# SH2_-_MCU.net
KiCad netlist of a schematic drawn in Altium Designer
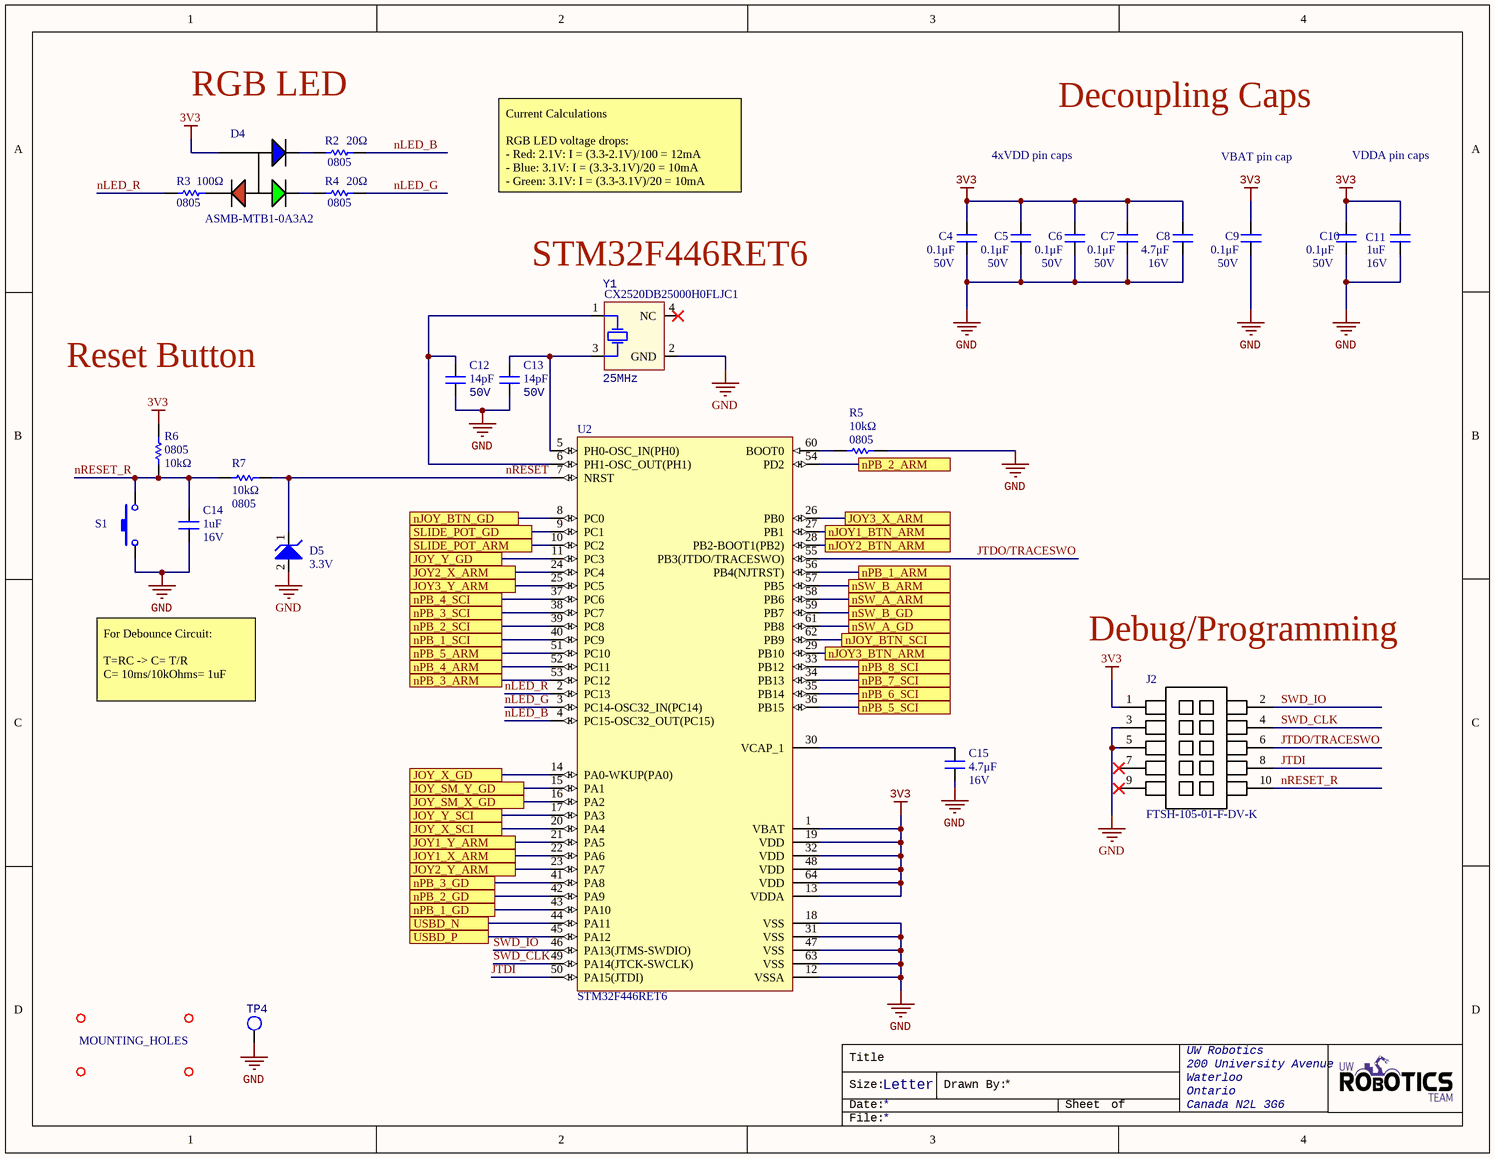
[diagram p0: SH2 - MCU.SchDoc]

(export (version "E")
  (design (tool "Eeschema 10.0.6"))
  (components
    (comp (ref "C4")
      (value "0.1μF")
      (footprint "CAPC2012X140N")
      (description "CAP CER 0.1UF 50V X7R 0805")
      (fields (field (name "TOLERANCE") "10%") (field (name "VOLTAGE RATING") "50V"))
      (libsource (lib "UWRT_Schematic_Library_2020") (part "CAP_0.1uF_50V_0805"))
    )
    (comp (ref "C5")
      (value "0.1μF")
      (footprint "CAPC2012X140N")
      (description "CAP CER 0.1UF 50V X7R 0805")
      (fields (field (name "TOLERANCE") "10%") (field (name "VOLTAGE RATING") "50V"))
      (libsource (lib "UWRT_Schematic_Library_2020") (part "CAP_0.1uF_50V_0805"))
    )
    (comp (ref "C6")
      (value "0.1μF")
      (footprint "CAPC2012X140N")
      (description "CAP CER 0.1UF 50V X7R 0805")
      (fields (field (name "TOLERANCE") "10%") (field (name "VOLTAGE RATING") "50V"))
      (libsource (lib "UWRT_Schematic_Library_2020") (part "CAP_0.1uF_50V_0805"))
    )
    (comp (ref "C7")
      (value "0.1μF")
      (footprint "CAPC2012X140N")
      (description "CAP CER 0.1UF 50V X7R 0805")
      (fields (field (name "TOLERANCE") "10%") (field (name "VOLTAGE RATING") "50V"))
      (libsource (lib "UWRT_Schematic_Library_2020") (part "CAP_0.1uF_50V_0805"))
    )
    (comp (ref "C8")
      (value "4.7μF")
      (footprint "CAPC2012X140N")
      (description "CAP CER 4.7UF 16V X5R 0805")
      (fields
        (field (name "TOLERANCE") "10%")
        (field (name "VOLTAGE RATING") "16V")
        (field (name "Comment") "CAP_4.7uF_16V_0805")
      )
      (libsource (lib "UWRT_Schematic_Library_2020") (part "CAP_4.7uF_16V_0805"))
    )
    (comp (ref "C9")
      (value "0.1μF")
      (footprint "CAPC2012X140N")
      (description "CAP CER 0.1UF 50V X7R 0805")
      (fields (field (name "TOLERANCE") "10%") (field (name "VOLTAGE RATING") "50V"))
      (libsource (lib "UWRT_Schematic_Library_2020") (part "CAP_0.1uF_50V_0805"))
    )
    (comp (ref "C10")
      (value "0.1μF")
      (footprint "CAPC2012X140N")
      (description "CAP CER 0.1UF 50V X7R 0805")
      (fields (field (name "TOLERANCE") "10%") (field (name "VOLTAGE RATING") "50V"))
      (libsource (lib "UWRT_Schematic_Library_2020") (part "CAP_0.1uF_50V_0805"))
    )
    (comp (ref "C11")
      (value "1uF")
      (footprint "CAPC2012X140N")
      (description "CAP CER 1UF 16V X7R 0805")
      (fields
        (field (name "TOLERANCE") "10%")
        (field (name "VOLTAGE RATING") "16V")
        (field (name "Comment") "CAP_1uF_16V_0805")
      )
      (libsource (lib "UWRT_Schematic_Library_2020") (part "CAP_1uF_16V_0805"))
    )
    (comp (ref "C12")
      (value "14pF")
      (footprint "CAPC0603(1608)55_N")
      (description "Cap Ceramic 14pF 50V C0G 5% SMD 0603 125C Cardboard T/R")
      (fields
        (field (name "TOLERANCE") "5%")
        (field (name "VOLTAGE RATING (DC)") "50V")
        (field (name "Comment") "CL10C140JB8NNNC")
      )
      (libsource (lib "UWRT_Schematic_Library_2020") (part "CL10C140JB8NNNC"))
    )
    (comp (ref "C13")
      (value "14pF")
      (footprint "CAPC0603(1608)55_N")
      (description "Cap Ceramic 14pF 50V C0G 5% SMD 0603 125C Cardboard T/R")
      (fields
        (field (name "TOLERANCE") "5%")
        (field (name "VOLTAGE RATING (DC)") "50V")
        (field (name "Comment") "CL10C140JB8NNNC")
      )
      (libsource (lib "UWRT_Schematic_Library_2020") (part "CL10C140JB8NNNC"))
    )
    (comp (ref "C14")
      (value "1uF")
      (footprint "CAPC2012X140N")
      (description "CAP CER 1UF 16V X7R 0805")
      (fields
        (field (name "TOLERANCE") "10%")
        (field (name "VOLTAGE RATING") "16V")
        (field (name "Comment") "CAP_1uF_16V_0805")
      )
      (libsource (lib "UWRT_Schematic_Library_2020") (part "CAP_1uF_16V_0805"))
    )
    (comp (ref "C15")
      (value "4.7μF")
      (footprint "CAPC2012X140N")
      (description "CAP CER 4.7UF 16V X5R 0805")
      (fields
        (field (name "TOLERANCE") "10%")
        (field (name "VOLTAGE RATING") "16V")
        (field (name "Comment") "CAP_4.7uF_16V_0805")
      )
      (libsource (lib "UWRT_Schematic_Library_2020") (part "CAP_4.7uF_16V_0805"))
    )
    (comp (ref "D4")
      (value "LED_RGB")
      (footprint "LED_RGB")
      (description "LED RGB DIFFUSED 4PLCC SMD")
      (fields (field (name "MANUFACTURER PART NUMBER 1") "ASMB-MTB1-0A3A2"))
      (libsource (lib "UWRT_Schematic_Library_2020") (part "LED_RGB"))
    )
    (comp (ref "D5")
      (value "TVS_DIODE_UNIDIR_3.3V")
      (footprint "SOD523")
      (description "TVS DIODE 3.3V 14.1V SOD523. Used to protect each connector input line going into the MCU.")
      (fields (field (name "REVERSE STANDOFF VOLTAGE") "3.3V"))
      (libsource (lib "UWRT_Schematic_Library_2020") (part "TVS_DIODE_UNIDIR_3.3V"))
    )
    (comp (ref "J2")
      (value "CON_PROGRAMMING")
      (footprint "FTSH-105-01-F-DV-K-P-TR")
      (fields (field (name "MANUFACTURER PART NUMBER 1") "FTSH-105-01-F-DV-K"))
      (libsource (lib "UWRT_Schematic_Library_2020") (part "CON_PROGRAMMING"))
    )
    (comp (ref "MH1")
      (value "MOUNTING_HOLES")
      (footprint "MOUNTING_HOLE")
      (description "6cm x 6cm")
      (libsource (lib "UWRT_Schematic_Library_2020") (part "MOUNTING_HOLES"))
    )
    (comp (ref "MH2")
      (value "MOUNTING_HOLES")
      (footprint "MOUNTING_HOLE")
      (description "6cm x 6cm")
      (libsource (lib "UWRT_Schematic_Library_2020") (part "MOUNTING_HOLES"))
    )
    (comp (ref "MH3")
      (value "MOUNTING_HOLES")
      (footprint "MOUNTING_HOLE")
      (description "6cm x 6cm")
      (libsource (lib "UWRT_Schematic_Library_2020") (part "MOUNTING_HOLES"))
    )
    (comp (ref "MH4")
      (value "MOUNTING_HOLES")
      (footprint "MOUNTING_HOLE")
      (description "6cm x 6cm")
      (libsource (lib "UWRT_Schematic_Library_2020") (part "MOUNTING_HOLES"))
    )
    (comp (ref "R2")
      (value "20Ω")
      (footprint "RESC2012X60N")
      (description "RES SMD 20 OHM 1% 1/8W 0805")
      (fields
        (field (name "CASE CODE (IMPERIAL)") "0805")
        (field (name "TOLERANCE") "1%")
        (field (name "Comment") "RES_20Ω_0805")
      )
      (libsource (lib "UWRT_Schematic_Library_2020") (part "RES_20Ω_0805"))
    )
    (comp (ref "R3")
      (value "100Ω")
      (footprint "RESC2012X60N")
      (description "RES SMD 100 OHM 1% 1/8W 0805")
      (fields (field (name "CASE CODE (IMPERIAL)") "0805") (field (name "Comment") "RES_100Ω_0805"))
      (libsource (lib "UWRT_Schematic_Library_2020") (part "RES_100Ω_0805"))
    )
    (comp (ref "R4")
      (value "20Ω")
      (footprint "RESC2012X60N")
      (description "RES SMD 20 OHM 1% 1/8W 0805")
      (fields
        (field (name "CASE CODE (IMPERIAL)") "0805")
        (field (name "TOLERANCE") "1%")
        (field (name "Comment") "RES_20Ω_0805")
      )
      (libsource (lib "UWRT_Schematic_Library_2020") (part "RES_20Ω_0805"))
    )
    (comp (ref "R5")
      (value "10kΩ")
      (footprint "RESC2012X60N")
      (description "RES SMD 10K OHM 1% 1/8W 0805")
      (fields
        (field (name "CASE CODE (IMPERIAL)") "0805")
        (field (name "TOLERANCE") "1%")
        (field (name "Comment") "RES_10kΩ_0805")
      )
      (libsource (lib "UWRT_Schematic_Library_2020") (part "RES_10kΩ_0805"))
    )
    (comp (ref "R6")
      (value "10kΩ")
      (footprint "RESC2012X60N")
      (description "RES SMD 10K OHM 1% 1/8W 0805")
      (fields
        (field (name "CASE CODE (IMPERIAL)") "0805")
        (field (name "TOLERANCE") "1%")
        (field (name "Comment") "RES_10kΩ_0805")
      )
      (libsource (lib "UWRT_Schematic_Library_2020") (part "RES_10kΩ_0805"))
    )
    (comp (ref "R7")
      (value "10kΩ")
      (footprint "RESC2012X60N")
      (description "RES SMD 10K OHM 1% 1/8W 0805")
      (fields
        (field (name "CASE CODE (IMPERIAL)") "0805")
        (field (name "TOLERANCE") "1%")
        (field (name "Comment") "RES_10kΩ_0805")
      )
      (libsource (lib "UWRT_Schematic_Library_2020") (part "RES_10kΩ_0805"))
    )
    (comp (ref "S1")
      (value "SW_TACTILE")
      (footprint "B3U-1000P")
      (description "Tactile Switch (Grey)")
      (libsource (lib "UWRT_Schematic_Library_2020") (part "SW_TACTILE"))
    )
    (comp (ref "TP4")
      (value "TESTPOINT_LOOP")
      (footprint "TESTPOINT_LOOP")
      (description "Loop testpoint through-hole pad")
      (libsource (lib "UWRT_Schematic_Library_2020") (part "TESTPOINT_LOOP"))
    )
    (comp (ref "U2")
      (value "STM32F446RET6")
      (footprint "STM-LQFP64_L")
      (libsource (lib "UWRT_Schematic_Library_2020") (part "MCU_STM32F446RET6"))
    )
    (comp (ref "Y1")
      (value "CRYSTAL_25MHZ")
      (footprint "SOIC254P1016X440-4N")
      (description "CRYSTAL 25.0000MHZ 12PF SMD")
      (fields
        (field (name "MANUFACTURER PART NUMBER 1") "CX2520DB25000H0FLJC1")
        (field (name "FREQUENCY") "25MHz")
      )
      (libsource (lib "UWRT_Schematic_Library_2020") (part "CRYSTAL_25MHZ"))
    )
  )
  (nets
    (net (code "1") (name "/JOY1_X_ARM") (class "Default")
      (node (ref "U2") (pin "22") (pinfunction "PA6_22") (pintype "bidirectional"))
    )
    (net (code "2") (name "/JOY1_Y_ARM") (class "Default")
      (node (ref "U2") (pin "21") (pinfunction "PA5_21") (pintype "bidirectional"))
    )
    (net (code "3") (name "/JOY2_X_ARM") (class "Default")
      (node (ref "U2") (pin "24") (pinfunction "PC4_24") (pintype "bidirectional"))
    )
    (net (code "4") (name "/JOY2_Y_ARM") (class "Default")
      (node (ref "U2") (pin "23") (pinfunction "PA7_23") (pintype "bidirectional"))
    )
    (net (code "5") (name "/JOY3_X_ARM") (class "Default")
      (node (ref "U2") (pin "26") (pinfunction "PB0_26") (pintype "bidirectional"))
    )
    (net (code "6") (name "/JOY3_Y_ARM") (class "Default")
      (node (ref "U2") (pin "25") (pinfunction "PC5_25") (pintype "bidirectional"))
    )
    (net (code "7") (name "/JOY_SM_X_GD") (class "Default")
      (node (ref "U2") (pin "16") (pinfunction "PA2_16") (pintype "bidirectional"))
    )
    (net (code "8") (name "/JOY_SM_Y_GD") (class "Default")
      (node (ref "U2") (pin "15") (pinfunction "PA1_15") (pintype "bidirectional"))
    )
    (net (code "9") (name "/JOY_X_GD") (class "Default")
      (node (ref "U2") (pin "14") (pinfunction "PA0-WKUP(PA0)_14") (pintype "bidirectional"))
    )
    (net (code "10") (name "/JOY_X_SCI") (class "Default")
      (node (ref "U2") (pin "20") (pinfunction "PA4_20") (pintype "bidirectional"))
    )
    (net (code "11") (name "/JOY_Y_GD") (class "Default")
      (node (ref "U2") (pin "11") (pinfunction "PC3_11") (pintype "bidirectional"))
    )
    (net (code "12") (name "/JOY_Y_SCI") (class "Default")
      (node (ref "U2") (pin "17") (pinfunction "PA3_17") (pintype "bidirectional"))
    )
    (net (code "13") (name "/JTDI") (class "Default")
      (node (ref "J2") (pin "8") (pinfunction "8_8") (pintype "passive"))
      (node (ref "U2") (pin "50") (pinfunction "PA15(JTDI)_50") (pintype "bidirectional"))
    )
    (net (code "14") (name "/JTDO{slash}TRACESWO") (class "Default")
      (node (ref "J2") (pin "6") (pinfunction "6_6") (pintype "passive"))
      (node (ref "U2") (pin "55") (pinfunction "PB3(JTDO/TRACESWO)_55") (pintype "bidirectional"))
    )
    (net (code "15") (name "/SLIDE_POT_ARM") (class "Default")
      (node (ref "U2") (pin "10") (pinfunction "PC2_10") (pintype "bidirectional"))
    )
    (net (code "16") (name "/SLIDE_POT_GD") (class "Default")
      (node (ref "U2") (pin "9") (pinfunction "PC1_9") (pintype "bidirectional"))
    )
    (net (code "17") (name "/SWD_CLK") (class "Default")
      (node (ref "J2") (pin "4") (pinfunction "4_4") (pintype "passive"))
      (node (ref "U2") (pin "49") (pinfunction "PA14(JTCK-SWCLK)_49") (pintype "bidirectional"))
    )
    (net (code "18") (name "/SWD_IO") (class "Default")
      (node (ref "J2") (pin "2") (pinfunction "2_2") (pintype "passive"))
      (node (ref "U2") (pin "46") (pinfunction "PA13(JTMS-SWDIO)_46") (pintype "bidirectional"))
    )
    (net (code "19") (name "/USBD_N") (class "Default")
      (node (ref "U2") (pin "44") (pinfunction "PA11_44") (pintype "bidirectional"))
    )
    (net (code "20") (name "/USBD_P") (class "Default")
      (node (ref "U2") (pin "45") (pinfunction "PA12_45") (pintype "bidirectional"))
    )
    (net (code "21") (name "/nJOY1_BTN_ARM") (class "Default")
      (node (ref "U2") (pin "27") (pinfunction "PB1_27") (pintype "bidirectional"))
    )
    (net (code "22") (name "/nJOY2_BTN_ARM") (class "Default")
      (node (ref "U2") (pin "28") (pinfunction "PB2-BOOT1(PB2)_28") (pintype "bidirectional"))
    )
    (net (code "23") (name "/nJOY3_BTN_ARM") (class "Default")
      (node (ref "U2") (pin "29") (pinfunction "PB10_29") (pintype "bidirectional"))
    )
    (net (code "24") (name "/nJOY_BTN_GD") (class "Default")
      (node (ref "U2") (pin "8") (pinfunction "PC0_8") (pintype "bidirectional"))
    )
    (net (code "25") (name "/nJOY_BTN_SCI") (class "Default")
      (node (ref "U2") (pin "62") (pinfunction "PB9_62") (pintype "bidirectional"))
    )
    (net (code "26") (name "/nLED_B") (class "Default")
      (node (ref "R2") (pin "2") (pinfunction "2_2") (pintype "passive"))
      (node (ref "U2") (pin "4") (pinfunction "PC15-OSC32_OUT(PC15)_4") (pintype "bidirectional"))
    )
    (net (code "27") (name "/nLED_G") (class "Default")
      (node (ref "R4") (pin "2") (pinfunction "2_2") (pintype "passive"))
      (node (ref "U2") (pin "3") (pinfunction "PC14-OSC32_IN(PC14)_3") (pintype "bidirectional"))
    )
    (net (code "28") (name "/nLED_R") (class "Default")
      (node (ref "R3") (pin "1") (pinfunction "1_1") (pintype "passive"))
      (node (ref "U2") (pin "2") (pinfunction "PC13_2") (pintype "bidirectional"))
    )
    (net (code "29") (name "/nPB_1_ARM") (class "Default")
      (node (ref "U2") (pin "56") (pinfunction "PB4(NJTRST)_56") (pintype "bidirectional"))
    )
    (net (code "30") (name "/nPB_1_GD") (class "Default")
      (node (ref "U2") (pin "43") (pinfunction "PA10_43") (pintype "bidirectional"))
    )
    (net (code "31") (name "/nPB_1_SCI") (class "Default")
      (node (ref "U2") (pin "40") (pinfunction "PC9_40") (pintype "bidirectional"))
    )
    (net (code "32") (name "/nPB_2_ARM") (class "Default")
      (node (ref "U2") (pin "54") (pinfunction "PD2_54") (pintype "bidirectional"))
    )
    (net (code "33") (name "/nPB_2_GD") (class "Default")
      (node (ref "U2") (pin "42") (pinfunction "PA9_42") (pintype "bidirectional"))
    )
    (net (code "34") (name "/nPB_2_SCI") (class "Default")
      (node (ref "U2") (pin "39") (pinfunction "PC8_39") (pintype "bidirectional"))
    )
    (net (code "35") (name "/nPB_3_ARM") (class "Default")
      (node (ref "U2") (pin "53") (pinfunction "PC12_53") (pintype "bidirectional"))
    )
    (net (code "36") (name "/nPB_3_GD") (class "Default")
      (node (ref "U2") (pin "41") (pinfunction "PA8_41") (pintype "bidirectional"))
    )
    (net (code "37") (name "/nPB_3_SCI") (class "Default")
      (node (ref "U2") (pin "38") (pinfunction "PC7_38") (pintype "bidirectional"))
    )
    (net (code "38") (name "/nPB_4_ARM") (class "Default")
      (node (ref "U2") (pin "52") (pinfunction "PC11_52") (pintype "bidirectional"))
    )
    (net (code "39") (name "/nPB_4_SCI") (class "Default")
      (node (ref "U2") (pin "37") (pinfunction "PC6_37") (pintype "bidirectional"))
    )
    (net (code "40") (name "/nPB_5_ARM") (class "Default")
      (node (ref "U2") (pin "51") (pinfunction "PC10_51") (pintype "bidirectional"))
    )
    (net (code "41") (name "/nPB_5_SCI") (class "Default")
      (node (ref "U2") (pin "36") (pinfunction "PB15_36") (pintype "bidirectional"))
    )
    (net (code "42") (name "/nPB_6_SCI") (class "Default")
      (node (ref "U2") (pin "35") (pinfunction "PB14_35") (pintype "bidirectional"))
    )
    (net (code "43") (name "/nPB_7_SCI") (class "Default")
      (node (ref "U2") (pin "34") (pinfunction "PB13_34") (pintype "bidirectional"))
    )
    (net (code "44") (name "/nPB_8_SCI") (class "Default")
      (node (ref "U2") (pin "33") (pinfunction "PB12_33") (pintype "bidirectional"))
    )
    (net (code "45") (name "/nRESET") (class "Default")
      (node (ref "D5") (pin "1") (pinfunction "1_1") (pintype "passive"))
      (node (ref "R7") (pin "2") (pinfunction "2_2") (pintype "passive"))
      (node (ref "U2") (pin "7") (pinfunction "NRST_7") (pintype "bidirectional"))
    )
    (net (code "46") (name "/nRESET_R") (class "Default")
      (node (ref "C14") (pin "2") (pinfunction "2_2") (pintype "passive"))
      (node (ref "J2") (pin "10") (pinfunction "10_10") (pintype "passive"))
      (node (ref "R6") (pin "1") (pinfunction "1_1") (pintype "passive"))
      (node (ref "R7") (pin "1") (pinfunction "1_1") (pintype "passive"))
      (node (ref "S1") (pin "1") (pinfunction "1_1") (pintype "passive"))
    )
    (net (code "47") (name "/nSW_A_ARM") (class "Default")
      (node (ref "U2") (pin "58") (pinfunction "PB6_58") (pintype "bidirectional"))
    )
    (net (code "48") (name "/nSW_A_GD") (class "Default")
      (node (ref "U2") (pin "61") (pinfunction "PB8_61") (pintype "bidirectional"))
    )
    (net (code "49") (name "/nSW_B_ARM") (class "Default")
      (node (ref "U2") (pin "57") (pinfunction "PB5_57") (pintype "bidirectional"))
    )
    (net (code "50") (name "/nSW_B_GD") (class "Default")
      (node (ref "U2") (pin "59") (pinfunction "PB7_59") (pintype "bidirectional"))
    )
    (net (code "51") (name "3V3") (class "Default")
      (node (ref "C10") (pin "2") (pinfunction "2_2") (pintype "passive"))
      (node (ref "C11") (pin "2") (pinfunction "2_2") (pintype "passive"))
      (node (ref "C4") (pin "2") (pinfunction "2_2") (pintype "passive"))
      (node (ref "C5") (pin "2") (pinfunction "2_2") (pintype "passive"))
      (node (ref "C6") (pin "2") (pinfunction "2_2") (pintype "passive"))
      (node (ref "C7") (pin "2") (pinfunction "2_2") (pintype "passive"))
      (node (ref "C8") (pin "2") (pinfunction "2_2") (pintype "passive"))
      (node (ref "C9") (pin "2") (pinfunction "2_2") (pintype "passive"))
      (node (ref "D4") (pin "4") (pinfunction "9_4") (pintype "passive"))
      (node (ref "J2") (pin "1") (pinfunction "1_1") (pintype "passive"))
      (node (ref "R6") (pin "2") (pinfunction "2_2") (pintype "passive"))
      (node (ref "U2") (pin "1") (pinfunction "VBAT_1") (pintype "power_in"))
      (node (ref "U2") (pin "13") (pinfunction "VDDA_13") (pintype "power_in"))
      (node (ref "U2") (pin "19") (pinfunction "VDD_19") (pintype "power_in"))
      (node (ref "U2") (pin "32") (pinfunction "VDD_32") (pintype "power_in"))
      (node (ref "U2") (pin "48") (pinfunction "VDD_48") (pintype "power_in"))
      (node (ref "U2") (pin "64") (pinfunction "VDD_64") (pintype "power_in"))
    )
    (net (code "52") (name "GND") (class "Default")
      (node (ref "C10") (pin "1") (pinfunction "1_1") (pintype "passive"))
      (node (ref "C11") (pin "1") (pinfunction "1_1") (pintype "passive"))
      (node (ref "C12") (pin "1") (pinfunction "1_1") (pintype "passive"))
      (node (ref "C13") (pin "1") (pinfunction "1_1") (pintype "passive"))
      (node (ref "C14") (pin "1") (pinfunction "1_1") (pintype "passive"))
      (node (ref "C15") (pin "1") (pinfunction "1_1") (pintype "passive"))
      (node (ref "C4") (pin "1") (pinfunction "1_1") (pintype "passive"))
      (node (ref "C5") (pin "1") (pinfunction "1_1") (pintype "passive"))
      (node (ref "C6") (pin "1") (pinfunction "1_1") (pintype "passive"))
      (node (ref "C7") (pin "1") (pinfunction "1_1") (pintype "passive"))
      (node (ref "C8") (pin "1") (pinfunction "1_1") (pintype "passive"))
      (node (ref "C9") (pin "1") (pinfunction "1_1") (pintype "passive"))
      (node (ref "D5") (pin "2") (pinfunction "2_2") (pintype "passive"))
      (node (ref "J2") (pin "3") (pinfunction "3_3") (pintype "passive"))
      (node (ref "J2") (pin "5") (pinfunction "5_5") (pintype "passive"))
      (node (ref "R5") (pin "2") (pinfunction "2_2") (pintype "passive"))
      (node (ref "S1") (pin "2") (pinfunction "2_2") (pintype "passive"))
      (node (ref "TP4") (pin "1") (pintype "passive"))
      (node (ref "U2") (pin "12") (pinfunction "VSSA_12") (pintype "power_in"))
      (node (ref "U2") (pin "18") (pinfunction "VSS_18") (pintype "power_in"))
      (node (ref "U2") (pin "31") (pinfunction "VSS_31") (pintype "power_in"))
      (node (ref "U2") (pin "47") (pinfunction "VSS_47") (pintype "power_in"))
      (node (ref "U2") (pin "63") (pinfunction "VSS_63") (pintype "power_in"))
      (node (ref "Y1") (pin "2") (pinfunction "GND_2") (pintype "power_in"))
    )
    (net (code "53") (name "Net-(D4-10)") (class "Default")
      (node (ref "D4") (pin "3") (pinfunction "10_3") (pintype "passive"))
      (node (ref "R2") (pin "1") (pinfunction "1_1") (pintype "passive"))
    )
    (net (code "54") (name "Net-(D4-11)") (class "Default")
      (node (ref "D4") (pin "1") (pinfunction "11_1") (pintype "passive"))
      (node (ref "R3") (pin "2") (pinfunction "2_2") (pintype "passive"))
    )
    (net (code "55") (name "Net-(D4-12)") (class "Default")
      (node (ref "D4") (pin "2") (pinfunction "12_2") (pintype "passive"))
      (node (ref "R4") (pin "1") (pinfunction "1_1") (pintype "passive"))
    )
    (net (code "56") (name "Net-(U2-BOOT0)") (class "Default")
      (node (ref "R5") (pin "1") (pinfunction "1_1") (pintype "passive"))
      (node (ref "U2") (pin "60") (pinfunction "BOOT0_60") (pintype "input"))
    )
    (net (code "57") (name "Net-(U2-PH0-OSC_IN(PH0))") (class "Default")
      (node (ref "C13") (pin "2") (pinfunction "2_2") (pintype "passive"))
      (node (ref "U2") (pin "5") (pinfunction "PH0-OSC_IN(PH0)_5") (pintype "bidirectional"))
      (node (ref "Y1") (pin "3") (pinfunction "HOT_3") (pintype "passive"))
    )
    (net (code "58") (name "Net-(U2-PH1-OSC_OUT(PH1))") (class "Default")
      (node (ref "C12") (pin "2") (pinfunction "2_2") (pintype "passive"))
      (node (ref "U2") (pin "6") (pinfunction "PH1-OSC_OUT(PH1)_6") (pintype "bidirectional"))
      (node (ref "Y1") (pin "1") (pinfunction "HOT_1") (pintype "passive"))
    )
    (net (code "59") (name "Net-(U2-VCAP_1)") (class "Default")
      (node (ref "C15") (pin "2") (pinfunction "2_2") (pintype "passive"))
      (node (ref "U2") (pin "30") (pinfunction "VCAP_1_30") (pintype "passive"))
    )
    (net (code "60") (name "unconnected-(J2-Pad7)") (class "Default")
      (node (ref "J2") (pin "7") (pinfunction "7_7") (pintype "passive+no_connect"))
    )
    (net (code "61") (name "unconnected-(J2-Pad9)") (class "Default")
      (node (ref "J2") (pin "9") (pinfunction "9_9") (pintype "passive+no_connect"))
    )
    (net (code "62") (name "unconnected-(Y1-NC-Pad4)") (class "Default")
      (node (ref "Y1") (pin "4") (pinfunction "NC_4") (pintype "passive+no_connect"))
    )
  )
)
